# scHnRk.net
KiCad netlist of a schematic drawn in EAGLE
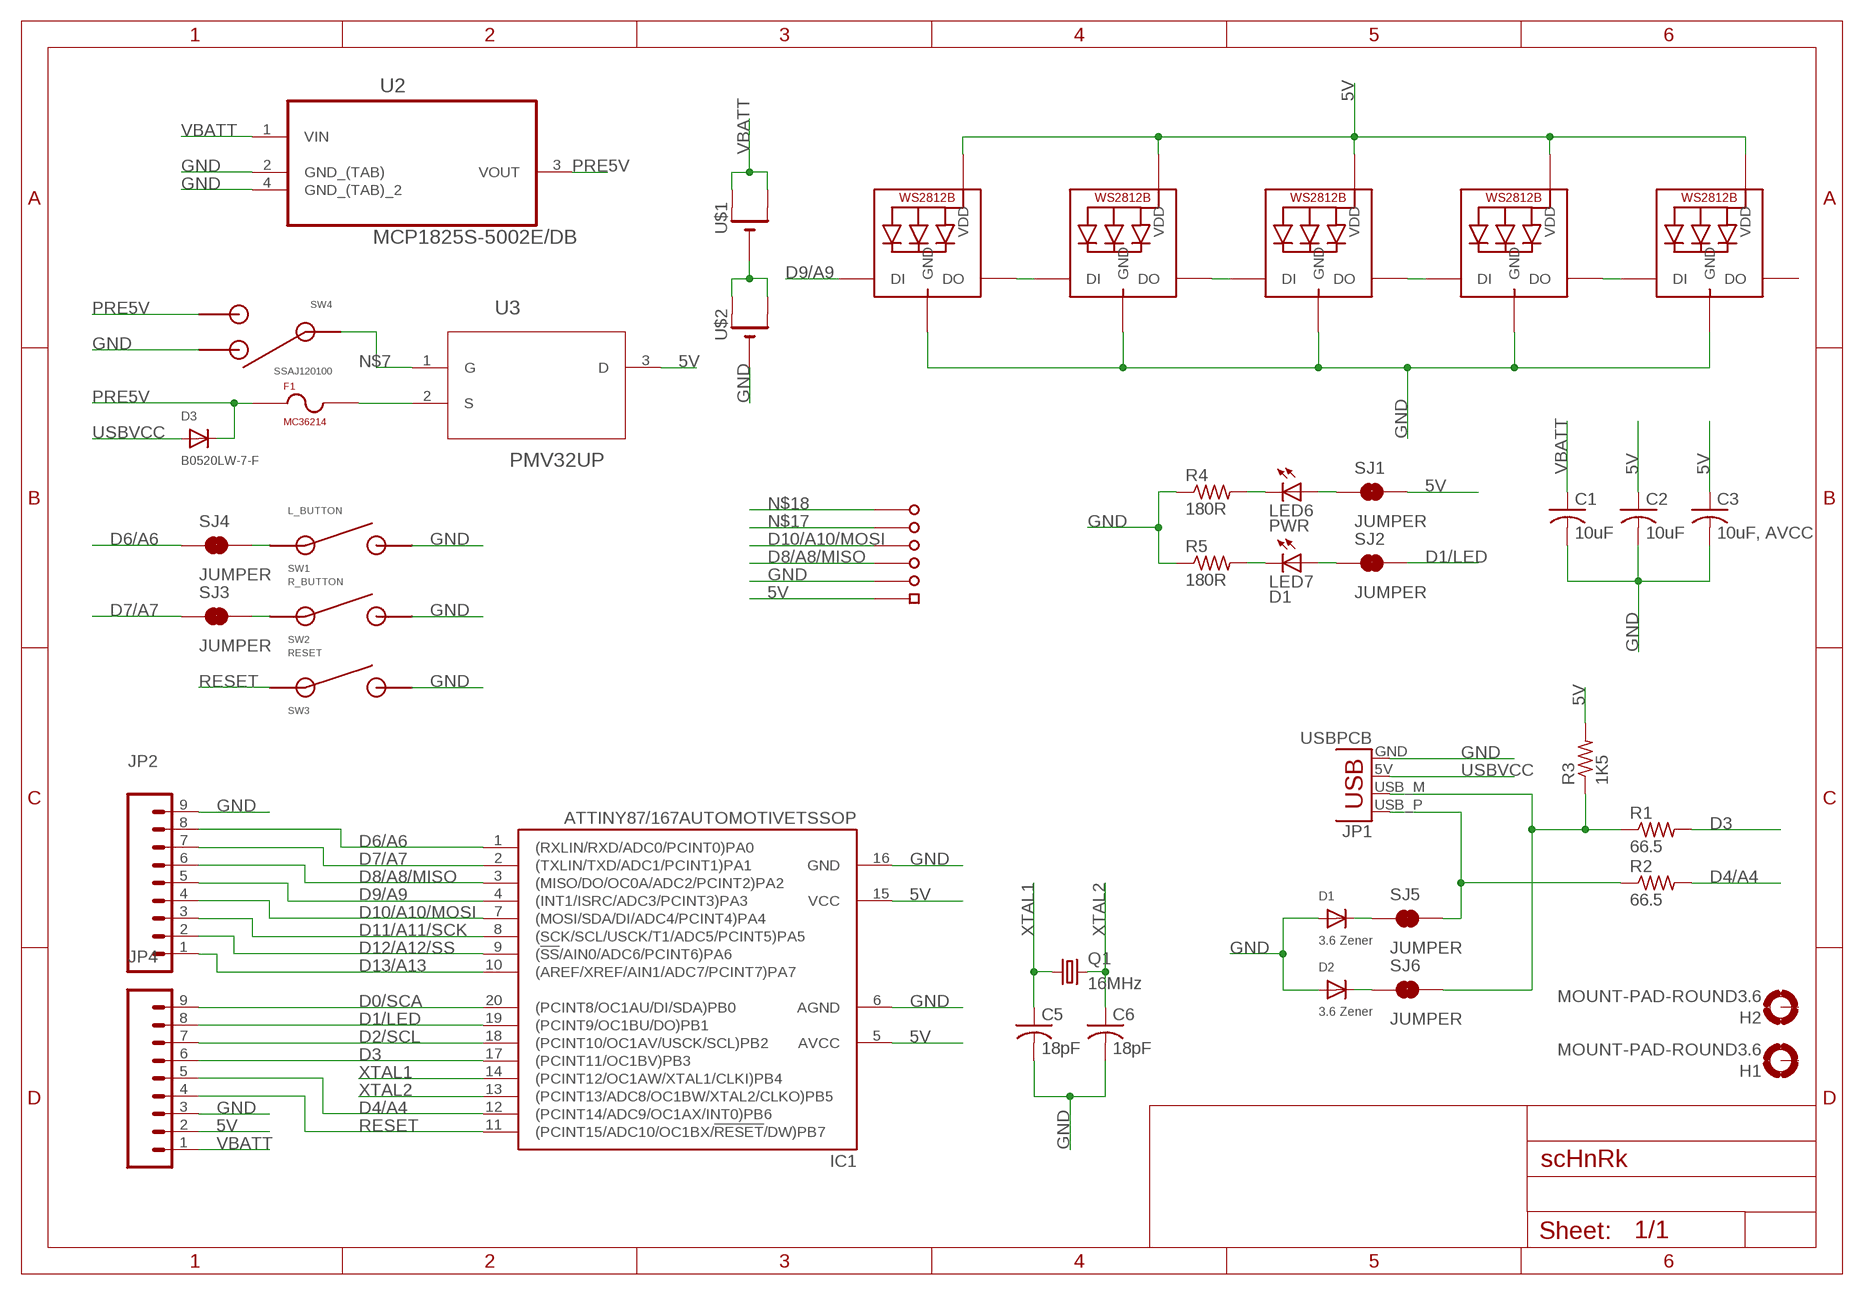
[diagram p0: schematic, sheet 1]

(export (version "E")
  (design (tool "Eeschema 10.0.6"))
  (components
    (comp (ref "C1")
      (value "10uF")
      (footprint "eagle-import:C1206K")
      (libsource (lib "eagle-import") (part "C-USC1206K"))
    )
    (comp (ref "C2")
      (value "10uF")
      (footprint "eagle-import:C1206K")
      (libsource (lib "eagle-import") (part "C-USC1206K"))
    )
    (comp (ref "C3")
      (value "10uF, AVCC")
      (footprint "eagle-import:C1206K")
      (libsource (lib "eagle-import") (part "C-USC1206K"))
    )
    (comp (ref "C5")
      (value "18pF")
      (footprint "eagle-import:C0603K")
      (libsource (lib "eagle-import") (part "C-USC0603K"))
    )
    (comp (ref "C6")
      (value "18pF")
      (footprint "eagle-import:C0603K")
      (libsource (lib "eagle-import") (part "C-USC0603K"))
    )
    (comp (ref "D1")
      (value "3.6 Zener")
      (footprint "eagle-import:SOD-523")
      (libsource (lib "eagle-import") (part "DIODESOD-523"))
    )
    (comp (ref "D2")
      (value "3.6 Zener")
      (footprint "eagle-import:SOD-523")
      (libsource (lib "eagle-import") (part "DIODESOD-523"))
    )
    (comp (ref "D3")
      (value "B0520LW-7-F")
      (footprint "eagle-import:SOD-123")
      (libsource (lib "eagle-import") (part "DIODESOD-123"))
    )
    (comp (ref "F1")
      (value "MC36214")
      (footprint "eagle-import:MC36214")
      (libsource (lib "eagle-import") (part "MC36214"))
    )
    (comp (ref "H1")
      (value "MOUNT-PAD-ROUND3.6")
      (footprint "eagle-import:3,6-PAD")
      (libsource (lib "eagle-import") (part "MOUNT-PAD-ROUND3.6"))
    )
    (comp (ref "H2")
      (value "MOUNT-PAD-ROUND3.6")
      (footprint "eagle-import:3,6-PAD")
      (libsource (lib "eagle-import") (part "MOUNT-PAD-ROUND3.6"))
    )
    (comp (ref "IC1")
      (value "ATTINY87/167AUTOMOTIVETSSOP")
      (footprint "eagle-import:TSSOP20")
      (libsource (lib "eagle-import") (part "ATTINY87/167AUTOMOTIVETSSOP"))
    )
    (comp (ref "JP1")
      (value "USBPCB")
      (footprint "eagle-import:USB-A-PCB")
      (libsource (lib "eagle-import") (part "USBPCB"))
    )
    (comp (ref "JP2")
      (value "M09")
      (footprint "eagle-import:1X09")
      (libsource (lib "eagle-import") (part "M09"))
    )
    (comp (ref "JP4")
      (value "M09")
      (footprint "eagle-import:1X09")
      (libsource (lib "eagle-import") (part "M09"))
    )
    (comp (ref "LED1")
      (value "WS2812B5050")
      (footprint "eagle-import:WS2812B")
      (libsource (lib "eagle-import") (part "WS2812B5050"))
    )
    (comp (ref "LED2")
      (value "WS2812B5050")
      (footprint "eagle-import:WS2812B")
      (libsource (lib "eagle-import") (part "WS2812B5050"))
    )
    (comp (ref "LED3")
      (value "WS2812B5050")
      (footprint "eagle-import:WS2812B")
      (libsource (lib "eagle-import") (part "WS2812B5050"))
    )
    (comp (ref "LED4")
      (value "WS2812B5050")
      (footprint "eagle-import:WS2812B")
      (libsource (lib "eagle-import") (part "WS2812B5050"))
    )
    (comp (ref "LED5")
      (value "WS2812B5050")
      (footprint "eagle-import:WS2812B")
      (libsource (lib "eagle-import") (part "WS2812B5050"))
    )
    (comp (ref "LED6")
      (value "PWR")
      (footprint "eagle-import:CHIPLED_0603")
      (libsource (lib "eagle-import") (part "LEDCHIPLED_0603"))
    )
    (comp (ref "LED7")
      (value "D1")
      (footprint "eagle-import:CHIPLED_0603")
      (libsource (lib "eagle-import") (part "LEDCHIPLED_0603"))
    )
    (comp (ref "Q1")
      (value "16MHz")
      (footprint "eagle-import:HC49UP")
      (libsource (lib "eagle-import") (part "CRYSTALHC49UP"))
    )
    (comp (ref "R1")
      (value "66.5")
      (footprint "eagle-import:R0603")
      (libsource (lib "eagle-import") (part "R-US_R0603"))
    )
    (comp (ref "R2")
      (value "66.5")
      (footprint "eagle-import:R0603")
      (libsource (lib "eagle-import") (part "R-US_R0603"))
    )
    (comp (ref "R3")
      (value "1K5")
      (footprint "eagle-import:R0603")
      (libsource (lib "eagle-import") (part "R-US_R0603"))
    )
    (comp (ref "R4")
      (value "180R")
      (footprint "eagle-import:R0603")
      (libsource (lib "eagle-import") (part "R-US_R0603"))
    )
    (comp (ref "R5")
      (value "180R")
      (footprint "eagle-import:R0603")
      (libsource (lib "eagle-import") (part "R-US_R0603"))
    )
    (comp (ref "SJ1")
      (value "JUMPER")
      (footprint "eagle-import:PAD-JUMPER-2-NC_BY_TRACE_YES_SILK")
      (libsource (lib "eagle-import") (part "JUMPER-PAD-2-NC_BY_TRACE"))
    )
    (comp (ref "SJ2")
      (value "JUMPER")
      (footprint "eagle-import:PAD-JUMPER-2-NC_BY_TRACE_YES_SILK")
      (libsource (lib "eagle-import") (part "JUMPER-PAD-2-NC_BY_TRACE"))
    )
    (comp (ref "SJ3")
      (value "JUMPER")
      (footprint "eagle-import:PAD-JUMPER-2-NC_BY_TRACE_YES_SILK")
      (libsource (lib "eagle-import") (part "JUMPER-PAD-2-NC_BY_TRACE"))
    )
    (comp (ref "SJ4")
      (value "JUMPER")
      (footprint "eagle-import:PAD-JUMPER-2-NC_BY_TRACE_YES_SILK")
      (libsource (lib "eagle-import") (part "JUMPER-PAD-2-NC_BY_TRACE"))
    )
    (comp (ref "SJ5")
      (value "JUMPER")
      (footprint "eagle-import:PAD-JUMPER-2-NC_BY_TRACE_YES_SILK")
      (libsource (lib "eagle-import") (part "JUMPER-PAD-2-NC_BY_TRACE"))
    )
    (comp (ref "SJ6")
      (value "JUMPER")
      (footprint "eagle-import:PAD-JUMPER-2-NC_BY_TRACE_YES_SILK")
      (libsource (lib "eagle-import") (part "JUMPER-PAD-2-NC_BY_TRACE"))
    )
    (comp (ref "SW1")
      (value "L_BUTTON")
      (footprint "eagle-import:SKRBAGE010")
      (libsource (lib "eagle-import") (part "SKRBAGE010"))
    )
    (comp (ref "SW2")
      (value "R_BUTTON")
      (footprint "eagle-import:SKRBAGE010")
      (libsource (lib "eagle-import") (part "SKRBAGE010"))
    )
    (comp (ref "SW3")
      (value "RESET")
      (footprint "eagle-import:SKRBAGE010")
      (libsource (lib "eagle-import") (part "SKRBAGE010"))
    )
    (comp (ref "SW4")
      (value "SSAJ120100")
      (footprint "eagle-import:SSAJ120100")
      (libsource (lib "eagle-import") (part "SSAJ120100"))
    )
    (comp (ref "TP1")
      (value "TP-R")
      (footprint "eagle-import:TP-R")
      (libsource (lib "eagle-import") (part "TP-R"))
    )
    (comp (ref "TP2")
      (value "TP-S")
      (footprint "eagle-import:TP_S")
      (libsource (lib "eagle-import") (part "TP-S"))
    )
    (comp (ref "TP3")
      (value "TP-R")
      (footprint "eagle-import:TP-R")
      (libsource (lib "eagle-import") (part "TP-R"))
    )
    (comp (ref "TP4")
      (value "TP-R")
      (footprint "eagle-import:TP-R")
      (libsource (lib "eagle-import") (part "TP-R"))
    )
    (comp (ref "TP5")
      (value "TP-R")
      (footprint "eagle-import:TP-R")
      (libsource (lib "eagle-import") (part "TP-R"))
    )
    (comp (ref "TP6")
      (value "TP-R")
      (footprint "eagle-import:TP-R")
      (libsource (lib "eagle-import") (part "TP-R"))
    )
    (comp (ref "U$1")
      (value "CR2032SMT")
      (footprint "eagle-import:CR2032-SMD")
      (libsource (lib "eagle-import") (part "CR2032SMT"))
    )
    (comp (ref "U$2")
      (value "CR2032SMT")
      (footprint "eagle-import:CR2032-SMD")
      (libsource (lib "eagle-import") (part "CR2032SMT"))
    )
    (comp (ref "U2")
      (value "MCP1825S-5002E/DB")
      (footprint "eagle-import:SOT230P700X180-4N")
      (libsource (lib "eagle-import") (part "MCP1825S-5002E/DB"))
    )
    (comp (ref "U3")
      (value "PMV32UP")
      (footprint "eagle-import:SOT95P230X110-3N")
      (libsource (lib "eagle-import") (part "PMV32UP"))
    )
  )
  (nets
    (net (code "1") (name "/5V") (class "Default")
      (node (ref "C2") (pin "1") (pinfunction "1_1") (pintype "passive"))
      (node (ref "C3") (pin "1") (pinfunction "1_1") (pintype "passive"))
      (node (ref "IC1") (pin "15") (pinfunction "VCC_15") (pintype "power_in"))
      (node (ref "IC1") (pin "5") (pinfunction "AVCC_5") (pintype "bidirectional"))
      (node (ref "JP4") (pin "2") (pinfunction "2_2") (pintype "passive"))
      (node (ref "LED1") (pin "1-VDD") (pinfunction "VDD_1-VDD") (pintype "power_in"))
      (node (ref "LED2") (pin "1-VDD") (pinfunction "VDD_1-VDD") (pintype "power_in"))
      (node (ref "LED3") (pin "1-VDD") (pinfunction "VDD_1-VDD") (pintype "power_in"))
      (node (ref "LED4") (pin "1-VDD") (pinfunction "VDD_1-VDD") (pintype "power_in"))
      (node (ref "LED5") (pin "1-VDD") (pinfunction "VDD_1-VDD") (pintype "power_in"))
      (node (ref "R3") (pin "2") (pinfunction "2_2") (pintype "passive"))
      (node (ref "SJ1") (pin "2") (pinfunction "2_2") (pintype "passive"))
      (node (ref "TP2") (pin "P$1") (pinfunction "P$1_P$1") (pintype "bidirectional"))
      (node (ref "U3") (pin "3") (pinfunction "D_3") (pintype "passive"))
    )
    (net (code "2") (name "/D0{slash}SCA") (class "Default")
      (node (ref "IC1") (pin "20") (pinfunction "(PCINT8/OC1AU/DI/SDA)PB0_20") (pintype "bidirectional"))
      (node (ref "JP4") (pin "9") (pinfunction "9_9") (pintype "passive"))
    )
    (net (code "3") (name "/D1{slash}LED") (class "Default")
      (node (ref "IC1") (pin "19") (pinfunction "(PCINT9/OC1BU/DO)PB1_19") (pintype "bidirectional"))
      (node (ref "JP4") (pin "8") (pinfunction "8_8") (pintype "passive"))
      (node (ref "SJ2") (pin "2") (pinfunction "2_2") (pintype "passive"))
    )
    (net (code "4") (name "/D2{slash}SCL") (class "Default")
      (node (ref "IC1") (pin "18") (pinfunction "(PCINT10/OC1AV/USCK/SCL)PB2_18") (pintype "bidirectional"))
      (node (ref "JP4") (pin "7") (pinfunction "7_7") (pintype "passive"))
    )
    (net (code "5") (name "/D3") (class "Default")
      (node (ref "IC1") (pin "17") (pinfunction "(PCINT11/OC1BV)PB3_17") (pintype "bidirectional"))
      (node (ref "JP4") (pin "6") (pinfunction "6_6") (pintype "passive"))
      (node (ref "R1") (pin "2") (pinfunction "2_2") (pintype "passive"))
    )
    (net (code "6") (name "/D4{slash}A4") (class "Default")
      (node (ref "IC1") (pin "12") (pinfunction "(PCINT14/ADC9/OC1AX/INT0)PB6_12") (pintype "bidirectional"))
      (node (ref "JP4") (pin "5") (pinfunction "5_5") (pintype "passive"))
      (node (ref "R2") (pin "2") (pinfunction "2_2") (pintype "passive"))
    )
    (net (code "7") (name "/D6{slash}A6") (class "Default")
      (node (ref "IC1") (pin "1") (pinfunction "(RXLIN/RXD/ADC0/PCINT0)PA0_1") (pintype "bidirectional"))
      (node (ref "JP2") (pin "8") (pinfunction "8_8") (pintype "passive"))
      (node (ref "SJ4") (pin "1") (pinfunction "1_1") (pintype "passive"))
    )
    (net (code "8") (name "/D7{slash}A7") (class "Default")
      (node (ref "IC1") (pin "2") (pinfunction "(TXLIN/TXD/ADC1/PCINT1)PA1_2") (pintype "bidirectional"))
      (node (ref "JP2") (pin "7") (pinfunction "7_7") (pintype "passive"))
      (node (ref "SJ3") (pin "1") (pinfunction "1_1") (pintype "passive"))
    )
    (net (code "9") (name "/D8{slash}A8{slash}MISO") (class "Default")
      (node (ref "IC1") (pin "3") (pinfunction "(MISO/DO/OC0A/ADC2/PCINT2)PA2_3") (pintype "bidirectional"))
      (node (ref "JP2") (pin "6") (pinfunction "6_6") (pintype "passive"))
      (node (ref "TP3") (pin "P$1") (pinfunction "P$1_P$1") (pintype "bidirectional"))
    )
    (net (code "10") (name "/D9{slash}A9") (class "Default")
      (node (ref "IC1") (pin "4") (pinfunction "(INT1/ISRC/ADC3/PCINT3)PA3_4") (pintype "bidirectional"))
      (node (ref "JP2") (pin "5") (pinfunction "5_5") (pintype "passive"))
      (node (ref "LED1") (pin "4-DIN") (pinfunction "DI_4-DIN") (pintype "input"))
    )
    (net (code "11") (name "/D10{slash}A10{slash}MOSI") (class "Default")
      (node (ref "IC1") (pin "7") (pinfunction "(MOSI/SDA/DI/ADC4/PCINT4)PA4_7") (pintype "bidirectional"))
      (node (ref "JP2") (pin "4") (pinfunction "4_4") (pintype "passive"))
      (node (ref "TP4") (pin "P$1") (pinfunction "P$1_P$1") (pintype "bidirectional"))
    )
    (net (code "12") (name "/D11{slash}A11{slash}SCK") (class "Default")
      (node (ref "IC1") (pin "8") (pinfunction "(SCK/SCL/USCK/T1/ADC5/PCINT5)PA5_8") (pintype "bidirectional"))
      (node (ref "JP2") (pin "3") (pinfunction "3_3") (pintype "passive"))
    )
    (net (code "13") (name "/D12{slash}A12{slash}SS") (class "Default")
      (node (ref "IC1") (pin "9") (pinfunction "(~{SS}/AIN0/ADC6/PCINT6)PA6_9") (pintype "bidirectional"))
      (node (ref "JP2") (pin "2") (pinfunction "2_2") (pintype "passive"))
    )
    (net (code "14") (name "/D13{slash}A13") (class "Default")
      (node (ref "IC1") (pin "10") (pinfunction "(AREF/XREF/AIN1/ADC7/PCINT7)PA7_10") (pintype "bidirectional"))
      (node (ref "JP2") (pin "1") (pinfunction "1_1") (pintype "passive"))
    )
    (net (code "15") (name "/GND") (class "Default")
      (node (ref "C1") (pin "2") (pinfunction "2_2") (pintype "passive"))
      (node (ref "C2") (pin "2") (pinfunction "2_2") (pintype "passive"))
      (node (ref "C3") (pin "2") (pinfunction "2_2") (pintype "passive"))
      (node (ref "C5") (pin "2") (pinfunction "2_2") (pintype "passive"))
      (node (ref "C6") (pin "2") (pinfunction "2_2") (pintype "passive"))
      (node (ref "D1") (pin "A") (pinfunction "A_A") (pintype "passive"))
      (node (ref "D2") (pin "A") (pinfunction "A_A") (pintype "passive"))
      (node (ref "IC1") (pin "16") (pinfunction "GND_16") (pintype "power_in"))
      (node (ref "IC1") (pin "6") (pinfunction "AGND_6") (pintype "bidirectional"))
      (node (ref "JP1") (pin "GND") (pinfunction "GND_GND") (pintype "bidirectional"))
      (node (ref "JP2") (pin "9") (pinfunction "9_9") (pintype "passive"))
      (node (ref "JP4") (pin "3") (pinfunction "3_3") (pintype "passive"))
      (node (ref "LED1") (pin "3-GND") (pinfunction "GND_3-GND") (pintype "power_in"))
      (node (ref "LED2") (pin "3-GND") (pinfunction "GND_3-GND") (pintype "power_in"))
      (node (ref "LED3") (pin "3-GND") (pinfunction "GND_3-GND") (pintype "power_in"))
      (node (ref "LED4") (pin "3-GND") (pinfunction "GND_3-GND") (pintype "power_in"))
      (node (ref "LED5") (pin "3-GND") (pinfunction "GND_3-GND") (pintype "power_in"))
      (node (ref "R4") (pin "1") (pinfunction "1_1") (pintype "passive"))
      (node (ref "R5") (pin "1") (pinfunction "1_1") (pintype "passive"))
      (node (ref "SW1") (pin "P$2") (pinfunction "P$2_P$2") (pintype "bidirectional"))
      (node (ref "SW1") (pin "P$4") (pinfunction "P$2_P$4") (pintype "bidirectional"))
      (node (ref "SW2") (pin "P$2") (pinfunction "P$2_P$2") (pintype "bidirectional"))
      (node (ref "SW2") (pin "P$4") (pinfunction "P$2_P$4") (pintype "bidirectional"))
      (node (ref "SW3") (pin "P$2") (pinfunction "P$2_P$2") (pintype "bidirectional"))
      (node (ref "SW3") (pin "P$4") (pinfunction "P$2_P$4") (pintype "bidirectional"))
      (node (ref "SW4") (pin "P$1") (pinfunction "P$1_P$1") (pintype "bidirectional"))
      (node (ref "TP1") (pin "P$1") (pinfunction "P$1_P$1") (pintype "bidirectional"))
      (node (ref "U$2") (pin "-") (pinfunction "-_-") (pintype "passive"))
      (node (ref "U2") (pin "2") (pinfunction "GND_(TAB)_2") (pintype "passive"))
      (node (ref "U2") (pin "4") (pinfunction "GND_(TAB)_2_4") (pintype "passive"))
    )
    (net (code "16") (name "/N$7") (class "Default")
      (node (ref "SW4") (pin "P$C") (pinfunction "P$C_P$C") (pintype "bidirectional"))
      (node (ref "U3") (pin "1") (pinfunction "G_1") (pintype "passive"))
    )
    (net (code "17") (name "/N$17") (class "Default")
      (node (ref "TP5") (pin "P$1") (pinfunction "P$1_P$1") (pintype "bidirectional"))
    )
    (net (code "18") (name "/N$18") (class "Default")
      (node (ref "TP6") (pin "P$1") (pinfunction "P$1_P$1") (pintype "bidirectional"))
    )
    (net (code "19") (name "/PRE5V") (class "Default")
      (node (ref "D3") (pin "C") (pinfunction "C_C") (pintype "passive"))
      (node (ref "F1") (pin "P$1") (pinfunction "P$1_P$1") (pintype "bidirectional"))
      (node (ref "SW4") (pin "P$2") (pinfunction "P$2_P$2") (pintype "bidirectional"))
      (node (ref "U2") (pin "3") (pinfunction "VOUT_3") (pintype "output"))
    )
    (net (code "20") (name "/RESET") (class "Default")
      (node (ref "IC1") (pin "11") (pinfunction "(PCINT15/ADC10/OC1BX/~{RESET}/DW)PB7_11") (pintype "bidirectional"))
      (node (ref "JP4") (pin "4") (pinfunction "4_4") (pintype "passive"))
      (node (ref "SW3") (pin "P$1") (pinfunction "P$1_P$1") (pintype "bidirectional"))
      (node (ref "SW3") (pin "P$3") (pinfunction "P$1_P$3") (pintype "bidirectional"))
    )
    (net (code "21") (name "/USBVCC") (class "Default")
      (node (ref "D3") (pin "A") (pinfunction "A_A") (pintype "passive"))
      (node (ref "JP1") (pin "5V") (pinfunction "VBUS_5V") (pintype "bidirectional"))
    )
    (net (code "22") (name "/VBATT") (class "Default")
      (node (ref "C1") (pin "1") (pinfunction "1_1") (pintype "passive"))
      (node (ref "JP4") (pin "1") (pinfunction "1_1") (pintype "passive"))
      (node (ref "U$1") (pin "+$1") (pinfunction "+_+$1") (pintype "passive"))
      (node (ref "U$1") (pin "+$2") (pinfunction "+1_+$2") (pintype "passive"))
      (node (ref "U2") (pin "1") (pinfunction "VIN_1") (pintype "input"))
    )
    (net (code "23") (name "/XTAL1") (class "Default")
      (node (ref "C5") (pin "1") (pinfunction "1_1") (pintype "passive"))
      (node (ref "IC1") (pin "14") (pinfunction "(PCINT12/OC1AW/XTAL1/CLKI)PB4_14") (pintype "bidirectional"))
      (node (ref "Q1") (pin "1") (pinfunction "1_1") (pintype "passive"))
    )
    (net (code "24") (name "/XTAL2") (class "Default")
      (node (ref "C6") (pin "1") (pinfunction "1_1") (pintype "passive"))
      (node (ref "IC1") (pin "13") (pinfunction "(PCINT13/ADC8/OC1BW/XTAL2/CLKO)PB5_13") (pintype "bidirectional"))
      (node (ref "Q1") (pin "2") (pinfunction "2_2") (pintype "passive"))
    )
    (net (code "25") (name "Net-(D1-C)") (class "Default")
      (node (ref "D1") (pin "K") (pinfunction "C_K") (pintype "passive"))
      (node (ref "SJ5") (pin "1") (pinfunction "1_1") (pintype "passive"))
    )
    (net (code "26") (name "Net-(D2-C)") (class "Default")
      (node (ref "D2") (pin "K") (pinfunction "C_K") (pintype "passive"))
      (node (ref "SJ6") (pin "1") (pinfunction "1_1") (pintype "passive"))
    )
    (net (code "27") (name "Net-(JP1-D+)") (class "Default")
      (node (ref "JP1") (pin "USB_P") (pinfunction "D+_USB_P") (pintype "bidirectional"))
      (node (ref "R2") (pin "1") (pinfunction "1_1") (pintype "passive"))
      (node (ref "SJ5") (pin "2") (pinfunction "2_2") (pintype "passive"))
    )
    (net (code "28") (name "Net-(JP1-D-)") (class "Default")
      (node (ref "JP1") (pin "USB_M") (pinfunction "D-_USB_M") (pintype "bidirectional"))
      (node (ref "R1") (pin "1") (pinfunction "1_1") (pintype "passive"))
      (node (ref "R3") (pin "1") (pinfunction "1_1") (pintype "passive"))
      (node (ref "SJ6") (pin "2") (pinfunction "2_2") (pintype "passive"))
    )
    (net (code "29") (name "Net-(LED1-DO)") (class "Default")
      (node (ref "LED1") (pin "2-DOUT") (pinfunction "DO_2-DOUT") (pintype "output"))
      (node (ref "LED2") (pin "4-DIN") (pinfunction "DI_4-DIN") (pintype "input"))
    )
    (net (code "30") (name "Net-(LED2-DO)") (class "Default")
      (node (ref "LED2") (pin "2-DOUT") (pinfunction "DO_2-DOUT") (pintype "output"))
      (node (ref "LED3") (pin "4-DIN") (pinfunction "DI_4-DIN") (pintype "input"))
    )
    (net (code "31") (name "Net-(LED3-DO)") (class "Default")
      (node (ref "LED3") (pin "2-DOUT") (pinfunction "DO_2-DOUT") (pintype "output"))
      (node (ref "LED4") (pin "4-DIN") (pinfunction "DI_4-DIN") (pintype "input"))
    )
    (net (code "32") (name "Net-(LED4-DO)") (class "Default")
      (node (ref "LED4") (pin "2-DOUT") (pinfunction "DO_2-DOUT") (pintype "output"))
      (node (ref "LED5") (pin "4-DIN") (pinfunction "DI_4-DIN") (pintype "input"))
    )
    (net (code "33") (name "Net-(LED6-PadA)") (class "Default")
      (node (ref "LED6") (pin "A") (pinfunction "A_A") (pintype "passive"))
      (node (ref "SJ1") (pin "1") (pinfunction "1_1") (pintype "passive"))
    )
    (net (code "34") (name "Net-(LED6-PadC)") (class "Default")
      (node (ref "LED6") (pin "C") (pinfunction "C_C") (pintype "passive"))
      (node (ref "R4") (pin "2") (pinfunction "2_2") (pintype "passive"))
    )
    (net (code "35") (name "Net-(LED7-PadA)") (class "Default")
      (node (ref "LED7") (pin "A") (pinfunction "A_A") (pintype "passive"))
      (node (ref "SJ2") (pin "1") (pinfunction "1_1") (pintype "passive"))
    )
    (net (code "36") (name "Net-(LED7-PadC)") (class "Default")
      (node (ref "LED7") (pin "C") (pinfunction "C_C") (pintype "passive"))
      (node (ref "R5") (pin "2") (pinfunction "2_2") (pintype "passive"))
    )
    (net (code "37") (name "Net-(SJ3-Pad2)") (class "Default")
      (node (ref "SJ3") (pin "2") (pinfunction "2_2") (pintype "passive"))
      (node (ref "SW2") (pin "P$1") (pinfunction "P$1_P$1") (pintype "bidirectional"))
      (node (ref "SW2") (pin "P$3") (pinfunction "P$1_P$3") (pintype "bidirectional"))
    )
    (net (code "38") (name "Net-(SJ4-Pad2)") (class "Default")
      (node (ref "SJ4") (pin "2") (pinfunction "2_2") (pintype "passive"))
      (node (ref "SW1") (pin "P$1") (pinfunction "P$1_P$1") (pintype "bidirectional"))
      (node (ref "SW1") (pin "P$3") (pinfunction "P$1_P$3") (pintype "bidirectional"))
    )
    (net (code "39") (name "Net-(U$2-+)") (class "Default")
      (node (ref "U$1") (pin "-") (pinfunction "-_-") (pintype "passive"))
      (node (ref "U$2") (pin "+$1") (pinfunction "+_+$1") (pintype "passive"))
      (node (ref "U$2") (pin "+$2") (pinfunction "+1_+$2") (pintype "passive"))
    )
    (net (code "40") (name "Net-(U3-S)") (class "Default")
      (node (ref "F1") (pin "P$2") (pinfunction "P$2_P$2") (pintype "bidirectional"))
      (node (ref "U3") (pin "2") (pinfunction "S_2") (pintype "passive"))
    )
    (net (code "41") (name "unconnected-(H1-MOUNT-PadB3,6)") (class "Default")
      (node (ref "H1") (pin "B3,6") (pinfunction "MOUNT_B3,6") (pintype "passive"))
    )
    (net (code "42") (name "unconnected-(H2-MOUNT-PadB3,6)") (class "Default")
      (node (ref "H2") (pin "B3,6") (pinfunction "MOUNT_B3,6") (pintype "passive"))
    )
    (net (code "43") (name "unconnected-(LED5-DO-Pad2-DOUT)") (class "Default")
      (node (ref "LED5") (pin "2-DOUT") (pinfunction "DO_2-DOUT") (pintype "output"))
    )
  )
)
